# nufsr-power.net
KiCad netlist of a schematic drawn in Altium Designer
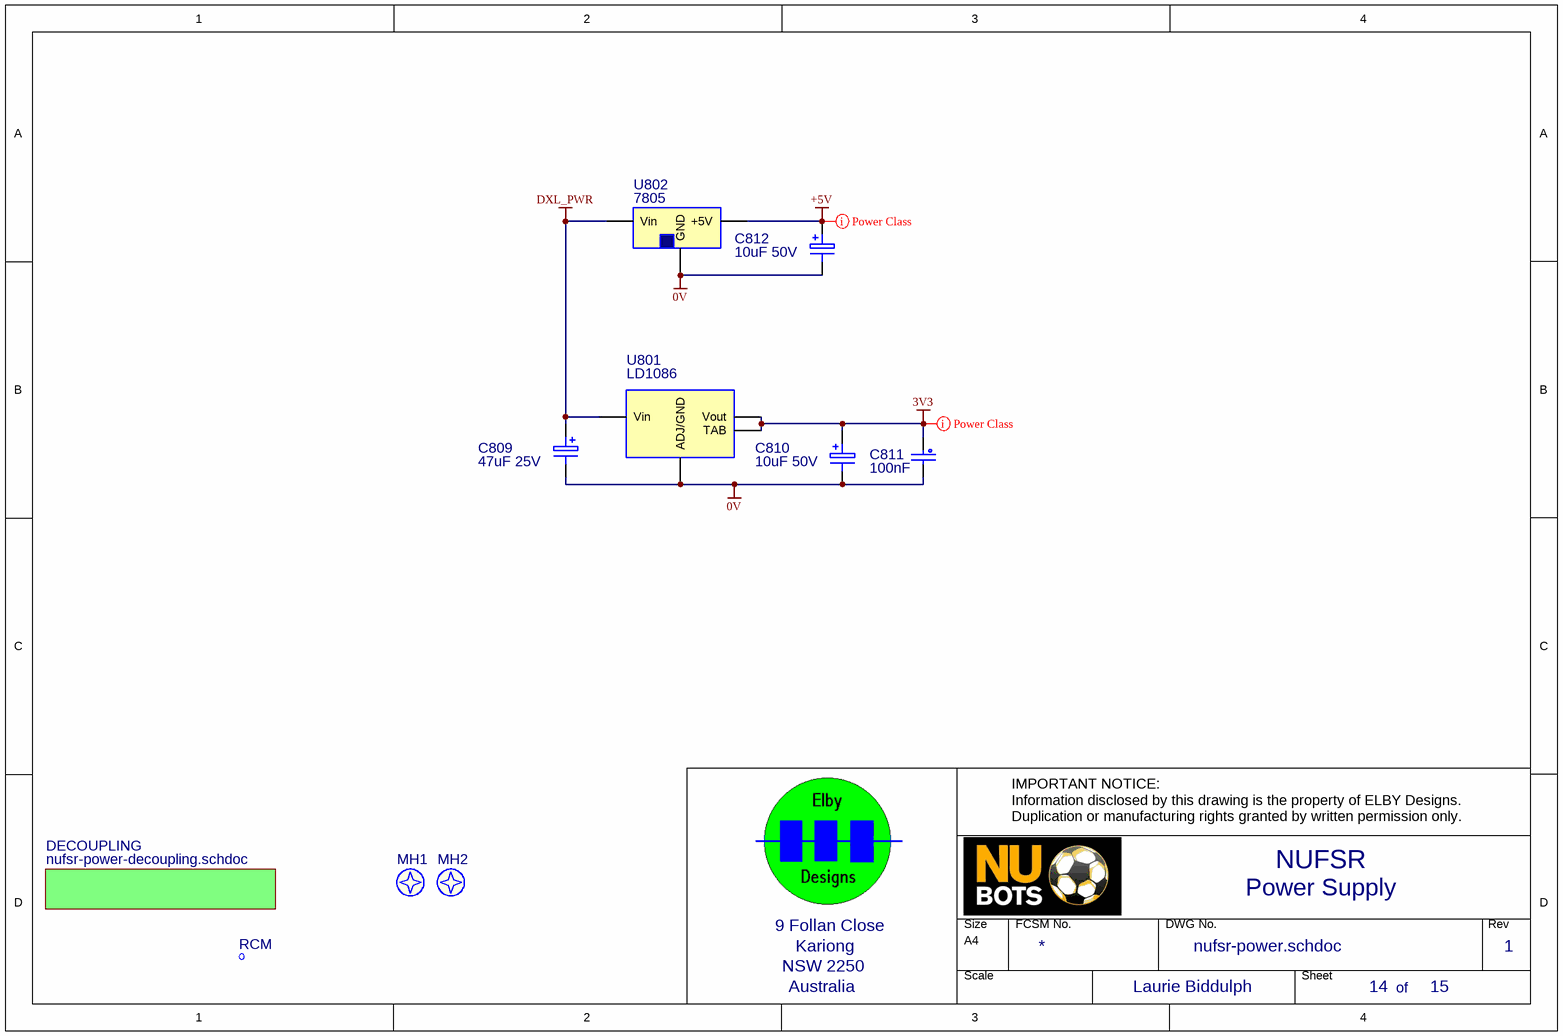
[diagram p0: nufsr-power.schdoc]

(export (version "E")
  (design (tool "Eeschema 10.0.6"))
  (components
    (comp (ref "C809")
      (value "47uF 25V")
      (footprint "CASE-D(LB)")
      (description "20% 35V Resin-dipped Tantalum")
      (libsource (lib "capacitor") (part "CT-47UF35V(LB)"))
    )
    (comp (ref "C810")
      (value "10uF 50V")
      (footprint "RB-D6.3-P2.5")
      (description "20% 50V Aluminium Electrolytic")
      (libsource (lib "capacitor") (part "CE-10UF50V(LB)"))
    )
    (comp (ref "C811")
      (value "100nF")
      (footprint "0603(LB)")
      (description "Monolithic Ceramic")
      (libsource (lib "capacitor") (part "CC-100NF(LB)"))
    )
    (comp (ref "C812")
      (value "10uF 50V")
      (footprint "RB-D6.3-P2.5")
      (description "20% 50V Aluminium Electrolytic")
      (libsource (lib "capacitor") (part "CE-10UF50V(LB)"))
    )
    (comp (ref "MH1")
      (value "Fixing")
      (footprint "HW-FIXING-3MM-PLASTIC")
      (description "M3/M4 Fixing Hole")
      (libsource (lib "hardware") (part "HW-FIXING-ISOLATED(LB)"))
    )
    (comp (ref "MH2")
      (value "Fixing")
      (footprint "HW-FIXING-3MM-PLASTIC")
      (description "M3/M4 Fixing Hole")
      (libsource (lib "hardware") (part "HW-FIXING-ISOLATED(LB)"))
    )
    (comp (ref "RCM")
      (value "HW-RCM(LB)")
      (footprint "HW-RCM")
      (description "N-Tick")
      (libsource (lib "hardware") (part "HW-RCM(LB)"))
    )
    (comp (ref "U801")
      (value "LD1086")
      (footprint "DPAK(LB)")
      (description "3-terminal Positive Voltage Regulator")
      (libsource (lib "ic") (part "LD1086(LB)"))
    )
    (comp (ref "U802")
      (value "7805")
      (footprint "DPAK(LB)")
      (description "3-terminal 1Amp Fixed Voltage Regulator")
      (libsource (lib "ic") (part "7805(LB)"))
    )
  )
  (nets
    (net (code "1") (name "+5V") (class "Default")
      (node (ref "C812") (pin "1") (pintype "passive"))
      (node (ref "U802") (pin "3") (pinfunction "+5V_3") (pintype "passive"))
    )
    (net (code "2") (name "0V") (class "Default")
      (node (ref "C809") (pin "2") (pintype "passive"))
      (node (ref "C810") (pin "2") (pintype "passive"))
      (node (ref "C811") (pin "2") (pintype "passive"))
      (node (ref "C812") (pin "2") (pintype "passive"))
      (node (ref "U801") (pin "1") (pinfunction "ADJ/GND_1") (pintype "passive"))
      (node (ref "U802") (pin "2") (pinfunction "GND_2") (pintype "passive"))
    )
    (net (code "3") (name "3V3") (class "Default")
      (node (ref "C810") (pin "1") (pintype "passive"))
      (node (ref "C811") (pin "1") (pintype "passive"))
      (node (ref "U801") (pin "2") (pinfunction "Vout_2") (pintype "passive"))
      (node (ref "U801") (pin "TAB") (pinfunction "TAB_TAB") (pintype "passive"))
    )
    (net (code "4") (name "DXL_PWR") (class "Default")
      (node (ref "C809") (pin "1") (pintype "passive"))
      (node (ref "U801") (pin "3") (pinfunction "Vin_3") (pintype "passive"))
      (node (ref "U802") (pin "1") (pinfunction "Vin_1") (pintype "passive"))
    )
    (net (code "5") (name "unconnected-(U802-PadTAB)") (class "Default")
      (node (ref "U802") (pin "TAB") (pinfunction "TAB_TAB") (pintype "passive"))
    )
  )
)
